# Own_18650_Board_v1_2_Final_AR.net
KiCad netlist of a schematic drawn in EAGLE
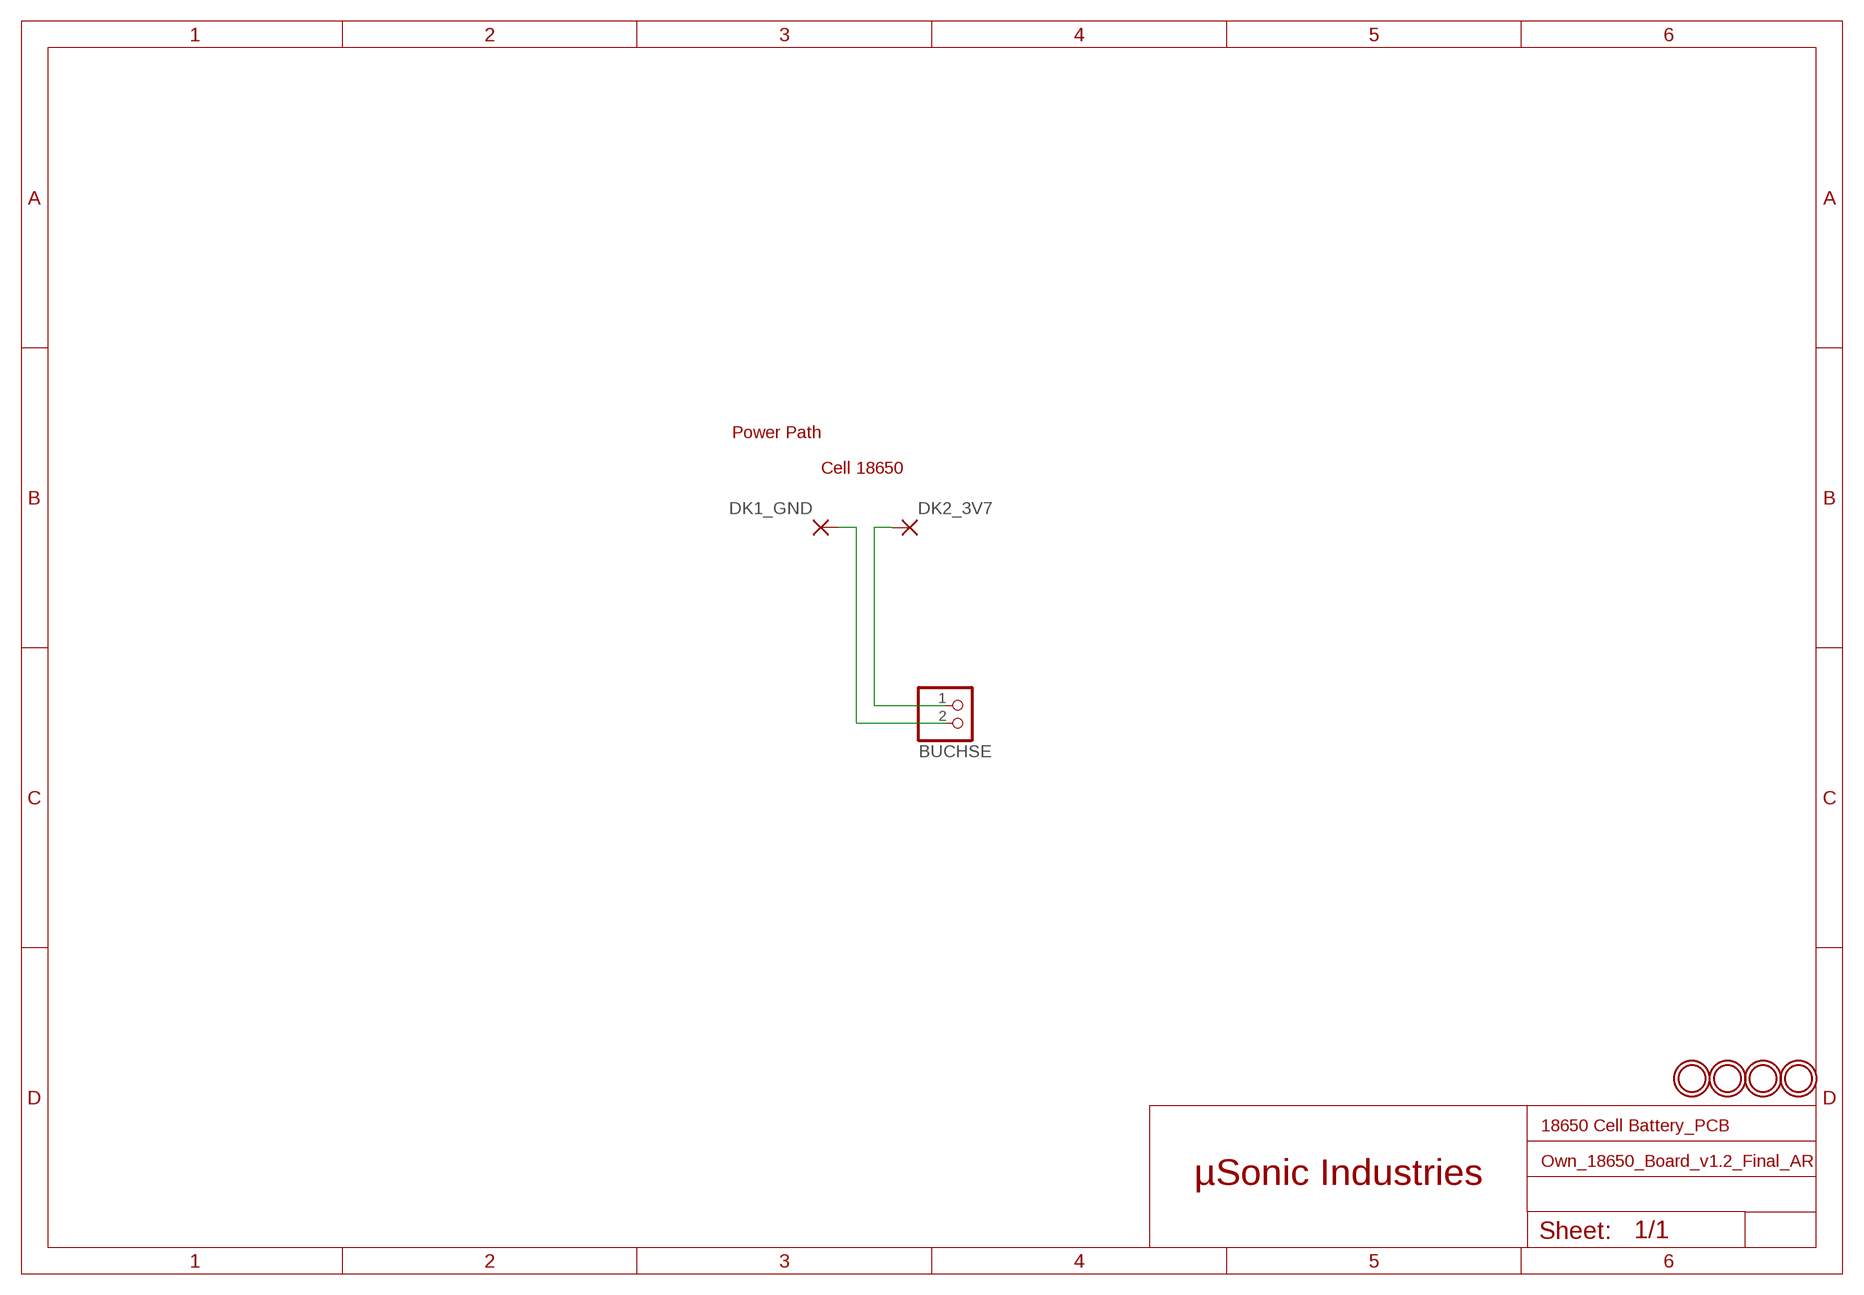
[diagram p0: schematic, sheet 1]

(export (version "E")
  (design (tool "Eeschema 10.0.6"))
  (components
    (comp (ref "BUCHSE")
      (value "JST_2PINOWN")
      (footprint "eagle-import:JST-PH-2-THMOWN")
      (libsource (lib "eagle-import") (part "JST_2PINOWN"))
    )
    (comp (ref "DK1_GND")
      (value "3,17/1,3")
      (footprint "eagle-import:3,17_1,3")
      (libsource (lib "eagle-import") (part "3,17/1,3"))
    )
    (comp (ref "DK2_3V7")
      (value "3,17/1,3")
      (footprint "eagle-import:3,17_1,3")
      (libsource (lib "eagle-import") (part "3,17/1,3"))
    )
    (comp (ref "U$1")
      (value "MOUNTINGHOLE2.5")
      (footprint "eagle-import:MOUNTINGHOLE_2.5_PLATED")
      (libsource (lib "eagle-import") (part "MOUNTINGHOLE2.5"))
    )
    (comp (ref "U$2")
      (value "MOUNTINGHOLE2.5")
      (footprint "eagle-import:MOUNTINGHOLE_2.5_PLATED")
      (libsource (lib "eagle-import") (part "MOUNTINGHOLE2.5"))
    )
    (comp (ref "U$3")
      (value "MOUNTINGHOLE2.5")
      (footprint "eagle-import:MOUNTINGHOLE_2.5_PLATED")
      (libsource (lib "eagle-import") (part "MOUNTINGHOLE2.5"))
    )
    (comp (ref "U$5")
      (value "MOUNTINGHOLE2.5")
      (footprint "eagle-import:MOUNTINGHOLE_2.5_PLATED")
      (libsource (lib "eagle-import") (part "MOUNTINGHOLE2.5"))
    )
  )
  (nets
    (net (code "1") (name "Net-(BUCHSE-1)") (class "Default")
      (node (ref "BUCHSE") (pin "2") (pinfunction "1_2") (pintype "passive"))
      (node (ref "DK1_GND") (pin "1") (pinfunction "P_1") (pintype "passive"))
    )
    (net (code "2") (name "Net-(BUCHSE-2)") (class "Default")
      (node (ref "BUCHSE") (pin "1") (pinfunction "2_1") (pintype "passive"))
      (node (ref "DK2_3V7") (pin "1") (pinfunction "P_1") (pintype "passive"))
    )
  )
)
